# eth.net
KiCad netlist of a schematic drawn in Altium Designer
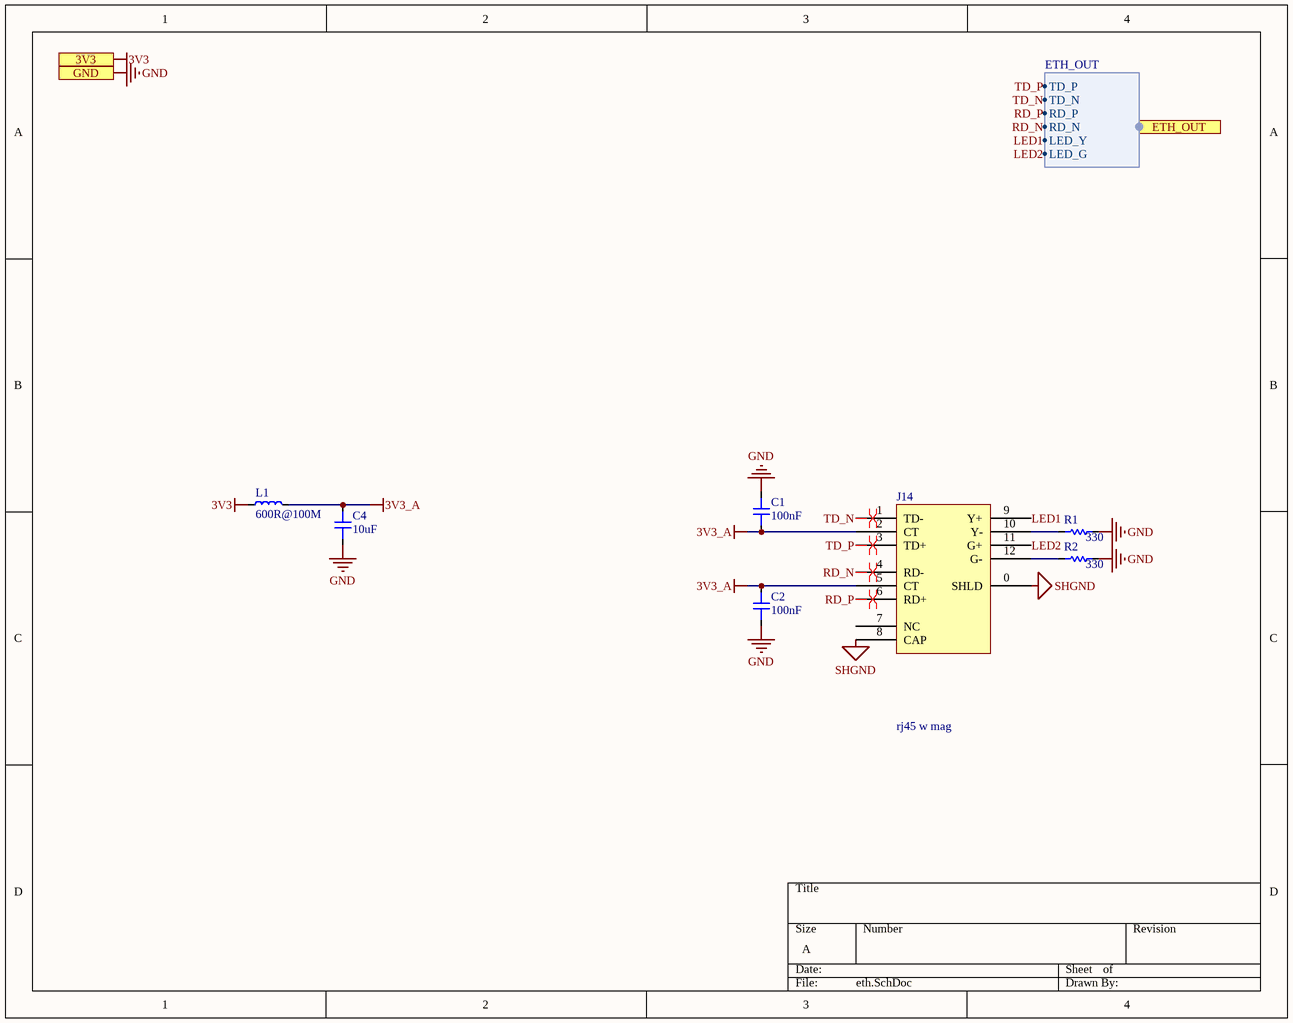
[diagram p0: eth.SchDoc]

(export (version "E")
  (design (tool "Eeschema 10.0.6"))
  (components
    (comp (ref "C1")
      (value "100nF")
      (footprint "CAP 0805 L")
      (description "CAP 0805")
      (libsource (lib "streetbot") (part "CAP 0805"))
    )
    (comp (ref "C2")
      (value "100nF")
      (footprint "CAP 0805 L")
      (description "CAP 0805")
      (libsource (lib "streetbot") (part "CAP 0805"))
    )
    (comp (ref "C4")
      (value "10uF")
      (footprint "CAP 0805 L")
      (description "CAP 0805")
      (libsource (lib "streetbot") (part "CAP 0805"))
    )
    (comp (ref "J14")
      (value "rj45 w mag")
      (footprint "CONN RJ45 MAG VERT")
      (description "Conn RJ-45 RCP 8 POS 2.54mm Solder ST Thru-Hole 12 Terminal 1 Port Tray")
      (libsource (lib "streetbot") (part "CONN rj45 mag vert"))
    )
    (comp (ref "L1")
      (value "600R@100M")
      (footprint "IND 0805 L")
      (description "IND 0805")
      (libsource (lib "streetbot") (part "IND 0805"))
    )
    (comp (ref "R1")
      (value "330")
      (footprint "RES 0603 L")
      (description "RES 0603")
      (libsource (lib "streetbot") (part "RES 0603"))
    )
    (comp (ref "R2")
      (value "330")
      (footprint "RES 0603 L")
      (description "RES 0603")
      (libsource (lib "streetbot") (part "RES 0603"))
    )
  )
  (nets
    (net (code "2") (name "/LED1") (class "Default")
      (node (ref "J14") (pin "9") (pinfunction "Y+_9") (pintype "passive"))
    )
    (net (code "3") (name "/LED2") (class "Default")
      (node (ref "J14") (pin "11") (pinfunction "G+_11") (pintype "passive"))
    )
    (net (code "4") (name "/RD_N") (class "Default")
      (node (ref "J14") (pin "4") (pinfunction "RD-_4") (pintype "passive"))
    )
    (net (code "5") (name "/RD_P") (class "Default")
      (node (ref "J14") (pin "6") (pinfunction "RD+_6") (pintype "passive"))
    )
    (net (code "6") (name "/TD_N") (class "Default")
      (node (ref "J14") (pin "1") (pinfunction "TD-_1") (pintype "passive"))
    )
    (net (code "7") (name "/TD_P") (class "Default")
      (node (ref "J14") (pin "3") (pinfunction "TD+_3") (pintype "passive"))
    )
    (net (code "9") (name "3V3") (class "Default")
      (node (ref "L1") (pin "1") (pinfunction "1_1") (pintype "passive"))
    )
    (net (code "10") (name "3V3_A") (class "Default")
      (node (ref "C1") (pin "1") (pinfunction "1_1") (pintype "passive"))
      (node (ref "C2") (pin "2") (pinfunction "2_2") (pintype "passive"))
      (node (ref "C4") (pin "2") (pinfunction "2_2") (pintype "passive"))
      (node (ref "J14") (pin "2") (pinfunction "CT_2") (pintype "passive"))
      (node (ref "J14") (pin "5") (pinfunction "CT_5") (pintype "passive"))
      (node (ref "L1") (pin "2") (pinfunction "2_2") (pintype "passive"))
    )
    (net (code "11") (name "GND") (class "Default")
      (node (ref "C1") (pin "2") (pinfunction "2_2") (pintype "passive"))
      (node (ref "C2") (pin "1") (pinfunction "1_1") (pintype "passive"))
      (node (ref "C4") (pin "1") (pinfunction "1_1") (pintype "passive"))
      (node (ref "R1") (pin "2") (pinfunction "2_2") (pintype "passive"))
      (node (ref "R2") (pin "2") (pinfunction "2_2") (pintype "passive"))
    )
    (net (code "12") (name "Net-(J14-G-)") (class "Default")
      (node (ref "J14") (pin "12") (pinfunction "G-_12") (pintype "passive"))
      (node (ref "R2") (pin "1") (pinfunction "1_1") (pintype "passive"))
    )
    (net (code "13") (name "Net-(J14-Y-)") (class "Default")
      (node (ref "J14") (pin "10") (pinfunction "Y-_10") (pintype "passive"))
      (node (ref "R1") (pin "1") (pinfunction "1_1") (pintype "passive"))
    )
    (net (code "14") (name "SHGND") (class "Default")
      (node (ref "J14") (pin "0") (pinfunction "SHLD_0") (pintype "passive"))
      (node (ref "J14") (pin "8") (pinfunction "CAP_8") (pintype "passive"))
    )
    (net (code "15") (name "unconnected-(J14-NC-Pad7)") (class "Default")
      (node (ref "J14") (pin "7") (pinfunction "NC_7") (pintype "passive"))
    )
  )
)
